# Power.net
KiCad netlist of a schematic drawn in Altium Designer
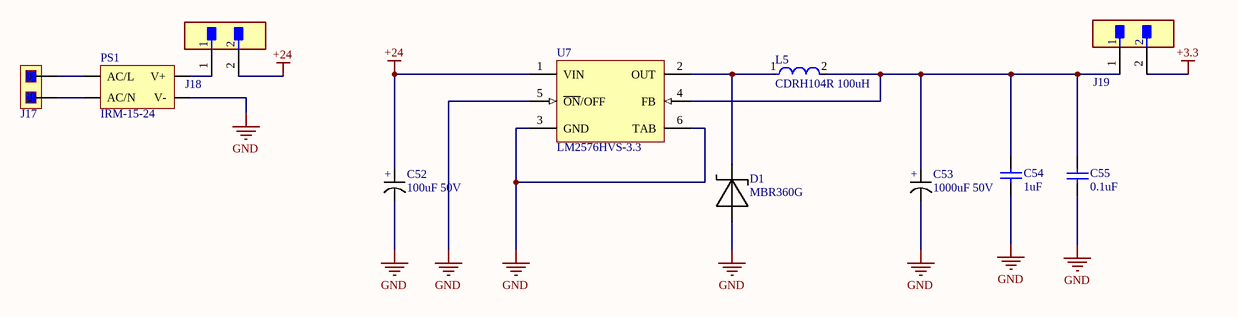
[diagram p0: Power.SchDoc]

(export (version "E")
  (design (tool "Eeschema 10.0.6"))
  (components
    (comp (ref "C52")
      (value "100uF 50V")
      (footprint "CAP VT 100uF 50V")
      (libsource (lib "Schemati_design") (part "Cap{colon} VT 100uF 50V"))
    )
    (comp (ref "C53")
      (value "1000uF 50V")
      (footprint "CAP: dip 1000uF 50V")
      (libsource (lib "Schemati_design") (part "Cap{colon} 1000uF 50V"))
    )
    (comp (ref "C54")
      (value "1uF")
      (footprint "CAPC2013X135X45ML10T25")
      (fields (field (name "MANUFACTURER") "Murata") (field (name "PART NUMBER") "GRM21BR72E103KW03L"))
      (libsource (lib "Altium Content Vault") (part "CAP"))
    )
    (comp (ref "C55")
      (value "0.1uF")
      (footprint "CAPC2013X135X45ML10T25")
      (fields (field (name "MANUFACTURER") "Murata") (field (name "PART NUMBER") "GRM21BR72E103KW03L"))
      (libsource (lib "Altium Content Vault") (part "CAP"))
    )
    (comp (ref "D1")
      (value "MBR360G")
      (footprint "MBR360G")
      (description "Rectifier Diode, Schottky, 1 Phase, 1 Element, 3A, 60V V(RRM), Silicon, DO-201AD")
      (fields (field (name "MANUFACTURER") "onsemi"))
      (libsource (lib "Schemati_design") (part "MBR360G"))
    )
    (comp (ref "J17")
      (value "KF301")
      (footprint "KF301-2P")
      (libsource (lib "Schemati_design") (part "KF301-5.0-2P"))
    )
    (comp (ref "J18")
      (value "M22-2510205")
      (footprint "FP-M22-2510205-MFG")
      (description "CONN HEADER VERT 2POS 2MM")
      (fields
        (field (name "MANUFACTURER") "Harwin")
        (field (name "OCTOPART") "https://octopart.com/m22-2510205-harwin-2538221")
      )
      (libsource (lib "Altium Content Vault") (part "3bc925449376181038e59eaffc5286c"))
    )
    (comp (ref "J19")
      (value "M22-2510205")
      (footprint "FP-M22-2510205-MFG")
      (description "CONN HEADER VERT 2POS 2MM")
      (fields
        (field (name "MANUFACTURER") "Harwin")
        (field (name "OCTOPART") "https://octopart.com/m22-2510205-harwin-2538221")
      )
      (libsource (lib "Altium Content Vault") (part "3bc925449376181038e59eaffc5286c"))
    )
    (comp (ref "L5")
      (value "CDRH104R 100uH")
      (footprint "FP-CDRH104R-MFG")
      (description "FIXED IND 5.2UH 6A 22 MOHM SMD")
      (fields (field (name "TOLERANCE") "30%"))
      (libsource (lib "Altium Content Vault") (part "725321dda6339637d4d059423bc1c3c"))
    )
    (comp (ref "PS1")
      (value "IRM-15-24")
      (footprint "IRM 15-24")
      (description "AC to DC Power Supply Encapsulated Single Output 24 Volts 0.63 Amps 15.12 Watts")
      (fields (field (name "MANUFACTURER") "Mean Well"))
      (libsource (lib "Schemati_design") (part "IRM-15-24"))
    )
    (comp (ref "U7")
      (value "LM2576HVS-3.3")
      (footprint "KTT0005B_L")
      (description "SIMPLE SWITCHER® 1A Step-Down Voltage Regulator, 5-pin TO-263, Pb-Free")
      (fields (field (name "MANUFACTURER") "Texas Instruments"))
      (libsource (lib "Altium Content Vault") (part "PM-REG-LM2575HVS-12"))
    )
  )
  (nets
    (net (code "1") (name "+3.3") (class "Default")
      (node (ref "J19") (pin "2") (pinfunction "2_2") (pintype "passive"))
    )
    (net (code "2") (name "+24") (class "Default")
      (node (ref "C52") (pin "1") (pinfunction "+_1") (pintype "passive"))
      (node (ref "J18") (pin "2") (pinfunction "2_2") (pintype "passive"))
      (node (ref "U7") (pin "1") (pinfunction "VIN_1") (pintype "power_in"))
    )
    (net (code "3") (name "GND") (class "Default")
      (node (ref "C52") (pin "2") (pinfunction "-_2") (pintype "passive"))
      (node (ref "C53") (pin "2") (pinfunction "-_2") (pintype "passive"))
      (node (ref "C54") (pin "1") (pinfunction "1_1") (pintype "passive"))
      (node (ref "C55") (pin "1") (pinfunction "1_1") (pintype "passive"))
      (node (ref "D1") (pin "1") (pinfunction "1_1") (pintype "passive"))
      (node (ref "PS1") (pin "3") (pinfunction "V-_3") (pintype "passive"))
      (node (ref "U7") (pin "3") (pinfunction "GND_3") (pintype "power_in"))
      (node (ref "U7") (pin "5") (pinfunction "~{ON}/OFF_5") (pintype "input"))
      (node (ref "U7") (pin "6") (pinfunction "TAB_6") (pintype "power_in"))
    )
    (net (code "4") (name "Net-(C53-+)") (class "Default")
      (node (ref "C53") (pin "1") (pinfunction "+_1") (pintype "passive"))
      (node (ref "C54") (pin "2") (pinfunction "2_2") (pintype "passive"))
      (node (ref "C55") (pin "2") (pinfunction "2_2") (pintype "passive"))
      (node (ref "J19") (pin "1") (pinfunction "1_1") (pintype "passive"))
      (node (ref "L5") (pin "2") (pinfunction "2_2") (pintype "passive"))
      (node (ref "U7") (pin "4") (pinfunction "FB_4") (pintype "input"))
    )
    (net (code "5") (name "Net-(PS1-AC{slash}L)") (class "Default")
      (node (ref "J17") (pin "1") (pinfunction "1_1") (pintype "passive"))
      (node (ref "PS1") (pin "1") (pinfunction "AC/L_1") (pintype "passive"))
    )
    (net (code "6") (name "Net-(PS1-AC{slash}N)") (class "Default")
      (node (ref "J17") (pin "2") (pinfunction "2_2") (pintype "passive"))
      (node (ref "PS1") (pin "2") (pinfunction "AC/N_2") (pintype "passive"))
    )
    (net (code "7") (name "Net-(PS1-V+)") (class "Default")
      (node (ref "J18") (pin "1") (pinfunction "1_1") (pintype "passive"))
      (node (ref "PS1") (pin "4") (pinfunction "V+_4") (pintype "passive"))
    )
    (net (code "8") (name "Net-(U7-OUT)") (class "Default")
      (node (ref "D1") (pin "2") (pinfunction "2_2") (pintype "passive"))
      (node (ref "L5") (pin "1") (pinfunction "1_1") (pintype "passive"))
      (node (ref "U7") (pin "2") (pinfunction "OUT_2") (pintype "power_in"))
    )
  )
)
